# Group_Project_PCB_Updated.net
KiCad netlist of a schematic drawn in EAGLE
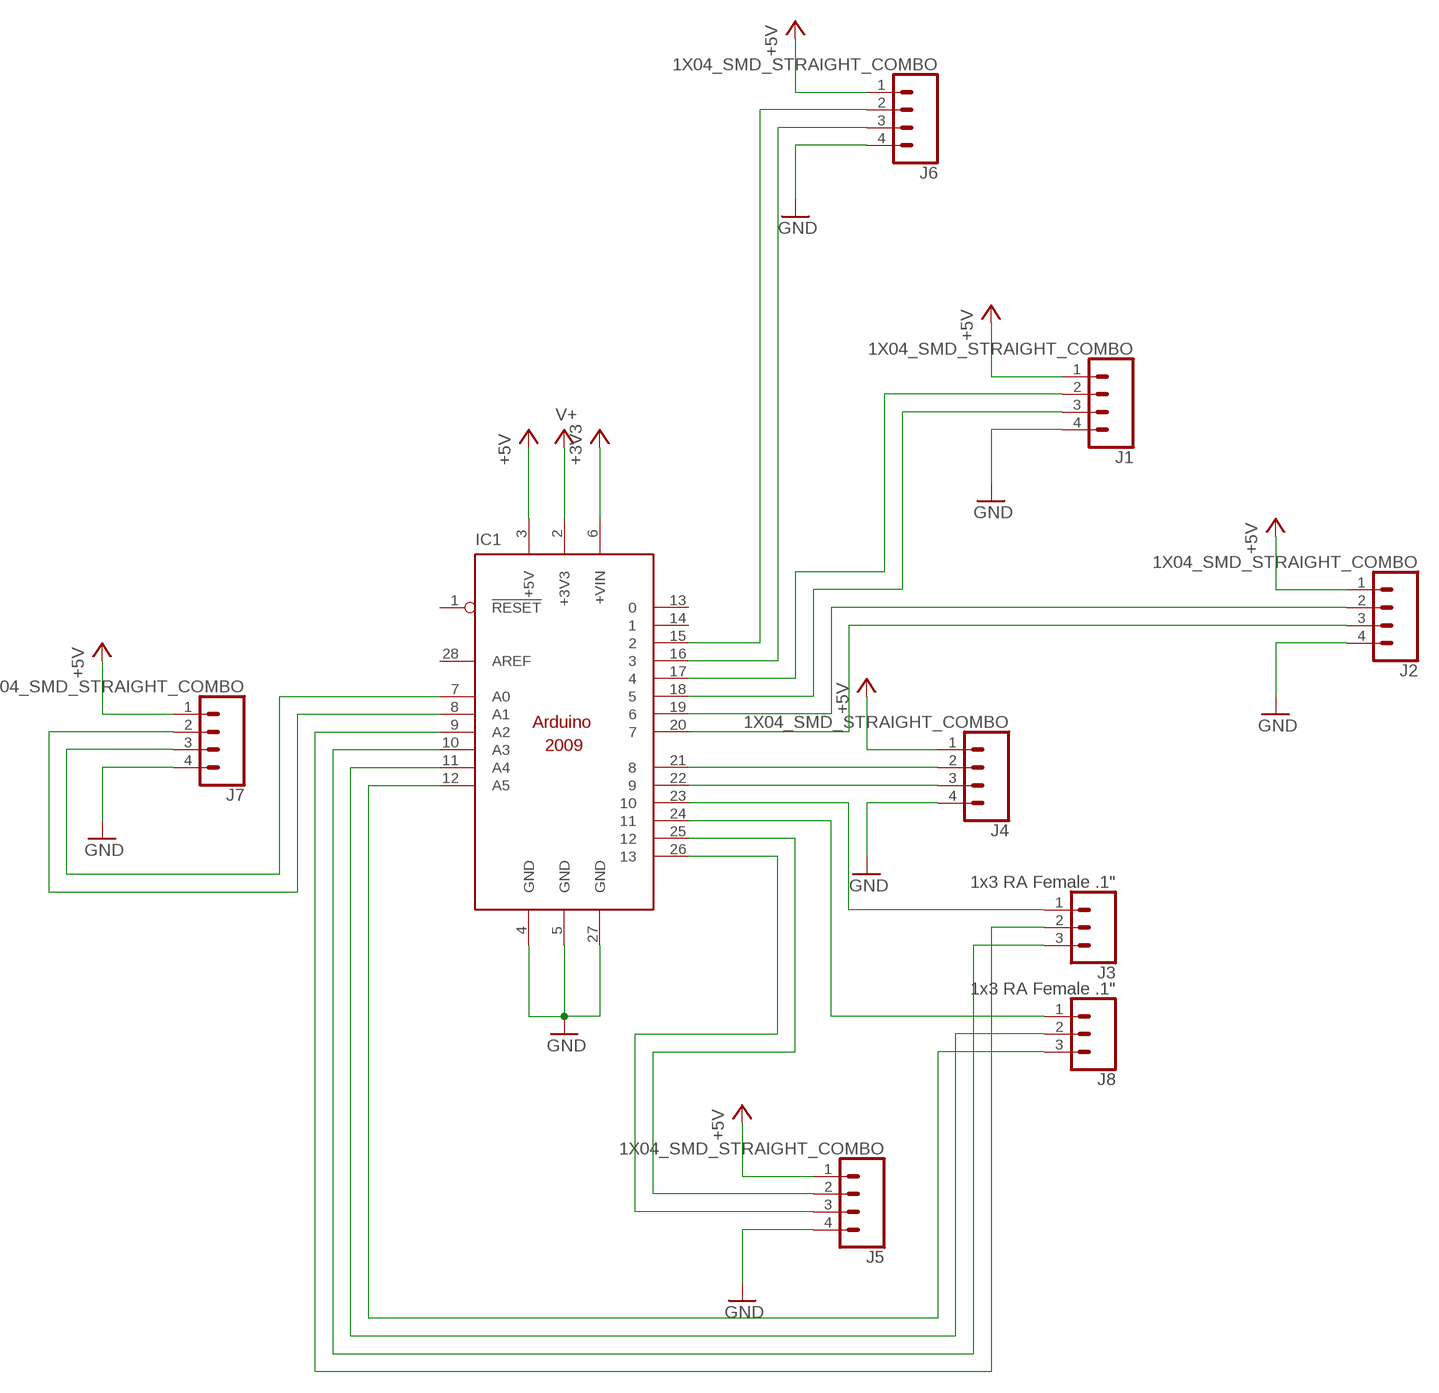
[diagram p0: schematic, sheet 1]

(export (version "E")
  (design (tool "Eeschema 10.0.6"))
  (components
    (comp (ref "IC1")
      (value "ARDUINO2009_10")
      (footprint "eagle-import:ARDUINO2009")
      (libsource (lib "eagle-import") (part "ARDUINO2009_10"))
    )
    (comp (ref "J1")
      (value "1X04_SMD_STRAIGHT_COMBO")
      (footprint "eagle-import:1X04_LONGPADS")
      (libsource (lib "eagle-import") (part "CONN_04LONGPADS"))
    )
    (comp (ref "J2")
      (value "1X04_SMD_STRAIGHT_COMBO")
      (footprint "eagle-import:1X04_LONGPADS")
      (libsource (lib "eagle-import") (part "CONN_04LONGPADS"))
    )
    (comp (ref "J3")
      (value "1x3 RA Female .1\"")
      (footprint "eagle-import:1X03_LONGPADS")
      (libsource (lib "eagle-import") (part "CONN_03LONGPADS"))
    )
    (comp (ref "J4")
      (value "1X04_SMD_STRAIGHT_COMBO")
      (footprint "eagle-import:1X04_LONGPADS")
      (libsource (lib "eagle-import") (part "CONN_04LONGPADS"))
    )
    (comp (ref "J5")
      (value "1X04_SMD_STRAIGHT_COMBO")
      (footprint "eagle-import:1X04_LONGPADS")
      (libsource (lib "eagle-import") (part "CONN_04LONGPADS"))
    )
    (comp (ref "J6")
      (value "1X04_SMD_STRAIGHT_COMBO")
      (footprint "eagle-import:1X04_LONGPADS")
      (libsource (lib "eagle-import") (part "CONN_04LONGPADS"))
    )
    (comp (ref "J7")
      (value "1X04_SMD_STRAIGHT_COMBO")
      (footprint "eagle-import:1X04_LONGPADS")
      (libsource (lib "eagle-import") (part "CONN_04LONGPADS"))
    )
    (comp (ref "J8")
      (value "1x3 RA Female .1\"")
      (footprint "eagle-import:1X03_LONGPADS")
      (libsource (lib "eagle-import") (part "CONN_03LONGPADS"))
    )
  )
  (nets
    (net (code "1") (name "+3V3") (class "Default")
      (node (ref "IC1") (pin "6") (pinfunction "+VIN_6") (pintype "bidirectional"))
    )
    (net (code "2") (name "+5V") (class "Default")
      (node (ref "IC1") (pin "3") (pinfunction "+5V_3") (pintype "power_in"))
      (node (ref "J1") (pin "1") (pinfunction "1_1") (pintype "passive"))
      (node (ref "J2") (pin "1") (pinfunction "1_1") (pintype "passive"))
      (node (ref "J4") (pin "1") (pinfunction "1_1") (pintype "passive"))
      (node (ref "J5") (pin "1") (pinfunction "1_1") (pintype "passive"))
      (node (ref "J6") (pin "1") (pinfunction "1_1") (pintype "passive"))
      (node (ref "J7") (pin "1") (pinfunction "1_1") (pintype "passive"))
    )
    (net (code "3") (name "GND") (class "Default")
      (node (ref "IC1") (pin "27") (pinfunction "GND_27") (pintype "power_in"))
      (node (ref "IC1") (pin "4") (pinfunction "GND_4") (pintype "power_in"))
      (node (ref "IC1") (pin "5") (pinfunction "GND_5") (pintype "power_in"))
      (node (ref "J1") (pin "4") (pinfunction "4_4") (pintype "passive"))
      (node (ref "J2") (pin "4") (pinfunction "4_4") (pintype "passive"))
      (node (ref "J4") (pin "4") (pinfunction "4_4") (pintype "passive"))
      (node (ref "J5") (pin "4") (pinfunction "4_4") (pintype "passive"))
      (node (ref "J6") (pin "4") (pinfunction "4_4") (pintype "passive"))
      (node (ref "J7") (pin "4") (pinfunction "4_4") (pintype "passive"))
    )
    (net (code "4") (name "Net-(IC1-2)") (class "Default")
      (node (ref "IC1") (pin "15") (pinfunction "2_15") (pintype "bidirectional"))
      (node (ref "J6") (pin "2") (pinfunction "2_2") (pintype "passive"))
    )
    (net (code "5") (name "Net-(IC1-3)") (class "Default")
      (node (ref "IC1") (pin "16") (pinfunction "3_16") (pintype "bidirectional"))
      (node (ref "J6") (pin "3") (pinfunction "3_3") (pintype "passive"))
    )
    (net (code "6") (name "Net-(IC1-4)") (class "Default")
      (node (ref "IC1") (pin "17") (pinfunction "4_17") (pintype "bidirectional"))
      (node (ref "J1") (pin "2") (pinfunction "2_2") (pintype "passive"))
    )
    (net (code "7") (name "Net-(IC1-5)") (class "Default")
      (node (ref "IC1") (pin "18") (pinfunction "5_18") (pintype "bidirectional"))
      (node (ref "J1") (pin "3") (pinfunction "3_3") (pintype "passive"))
    )
    (net (code "8") (name "Net-(IC1-6)") (class "Default")
      (node (ref "IC1") (pin "19") (pinfunction "6_19") (pintype "bidirectional"))
      (node (ref "J2") (pin "2") (pinfunction "2_2") (pintype "passive"))
    )
    (net (code "9") (name "Net-(IC1-7)") (class "Default")
      (node (ref "IC1") (pin "20") (pinfunction "7_20") (pintype "bidirectional"))
      (node (ref "J2") (pin "3") (pinfunction "3_3") (pintype "passive"))
    )
    (net (code "10") (name "Net-(IC1-8)") (class "Default")
      (node (ref "IC1") (pin "21") (pinfunction "8_21") (pintype "bidirectional"))
      (node (ref "J4") (pin "2") (pinfunction "2_2") (pintype "passive"))
    )
    (net (code "11") (name "Net-(IC1-9)") (class "Default")
      (node (ref "IC1") (pin "22") (pinfunction "9_22") (pintype "bidirectional"))
      (node (ref "J4") (pin "3") (pinfunction "3_3") (pintype "passive"))
    )
    (net (code "12") (name "Net-(IC1-10)") (class "Default")
      (node (ref "IC1") (pin "23") (pinfunction "10_23") (pintype "bidirectional"))
      (node (ref "J3") (pin "1") (pinfunction "1_1") (pintype "passive"))
    )
    (net (code "13") (name "Net-(IC1-11)") (class "Default")
      (node (ref "IC1") (pin "24") (pinfunction "11_24") (pintype "bidirectional"))
      (node (ref "J8") (pin "1") (pinfunction "1_1") (pintype "passive"))
    )
    (net (code "14") (name "Net-(IC1-12)") (class "Default")
      (node (ref "IC1") (pin "25") (pinfunction "12_25") (pintype "bidirectional"))
      (node (ref "J5") (pin "2") (pinfunction "2_2") (pintype "passive"))
    )
    (net (code "15") (name "Net-(IC1-13)") (class "Default")
      (node (ref "IC1") (pin "26") (pinfunction "13_26") (pintype "bidirectional"))
      (node (ref "J5") (pin "3") (pinfunction "3_3") (pintype "passive"))
    )
    (net (code "16") (name "Net-(IC1-A0)") (class "Default")
      (node (ref "IC1") (pin "7") (pinfunction "A0_7") (pintype "bidirectional"))
      (node (ref "J7") (pin "3") (pinfunction "3_3") (pintype "passive"))
    )
    (net (code "17") (name "Net-(IC1-A1)") (class "Default")
      (node (ref "IC1") (pin "8") (pinfunction "A1_8") (pintype "bidirectional"))
      (node (ref "J7") (pin "2") (pinfunction "2_2") (pintype "passive"))
    )
    (net (code "18") (name "Net-(IC1-A2)") (class "Default")
      (node (ref "IC1") (pin "9") (pinfunction "A2_9") (pintype "bidirectional"))
      (node (ref "J3") (pin "2") (pinfunction "2_2") (pintype "passive"))
    )
    (net (code "19") (name "Net-(IC1-A3)") (class "Default")
      (node (ref "IC1") (pin "10") (pinfunction "A3_10") (pintype "bidirectional"))
      (node (ref "J3") (pin "3") (pinfunction "3_3") (pintype "passive"))
    )
    (net (code "20") (name "Net-(IC1-A4)") (class "Default")
      (node (ref "IC1") (pin "11") (pinfunction "A4_11") (pintype "bidirectional"))
      (node (ref "J8") (pin "2") (pinfunction "2_2") (pintype "passive"))
    )
    (net (code "21") (name "Net-(IC1-A5)") (class "Default")
      (node (ref "IC1") (pin "12") (pinfunction "A5_12") (pintype "bidirectional"))
      (node (ref "J8") (pin "3") (pinfunction "3_3") (pintype "passive"))
    )
    (net (code "22") (name "V+") (class "Default")
      (node (ref "IC1") (pin "2") (pinfunction "+3V3_2") (pintype "power_in"))
    )
    (net (code "23") (name "unconnected-(IC1-0-Pad13)") (class "Default")
      (node (ref "IC1") (pin "13") (pinfunction "0_13") (pintype "bidirectional"))
    )
    (net (code "24") (name "unconnected-(IC1-1-Pad14)") (class "Default")
      (node (ref "IC1") (pin "14") (pinfunction "1_14") (pintype "bidirectional"))
    )
    (net (code "25") (name "unconnected-(IC1-AREF-Pad28)") (class "Default")
      (node (ref "IC1") (pin "28") (pinfunction "AREF_28") (pintype "bidirectional"))
    )
    (net (code "26") (name "unconnected-(IC1-~{RESET}-Pad1)") (class "Default")
      (node (ref "IC1") (pin "1") (pinfunction "~{RESET}_1") (pintype "bidirectional"))
    )
  )
)
